# laser_driver_fet.net
KiCad netlist of a schematic drawn in EAGLE
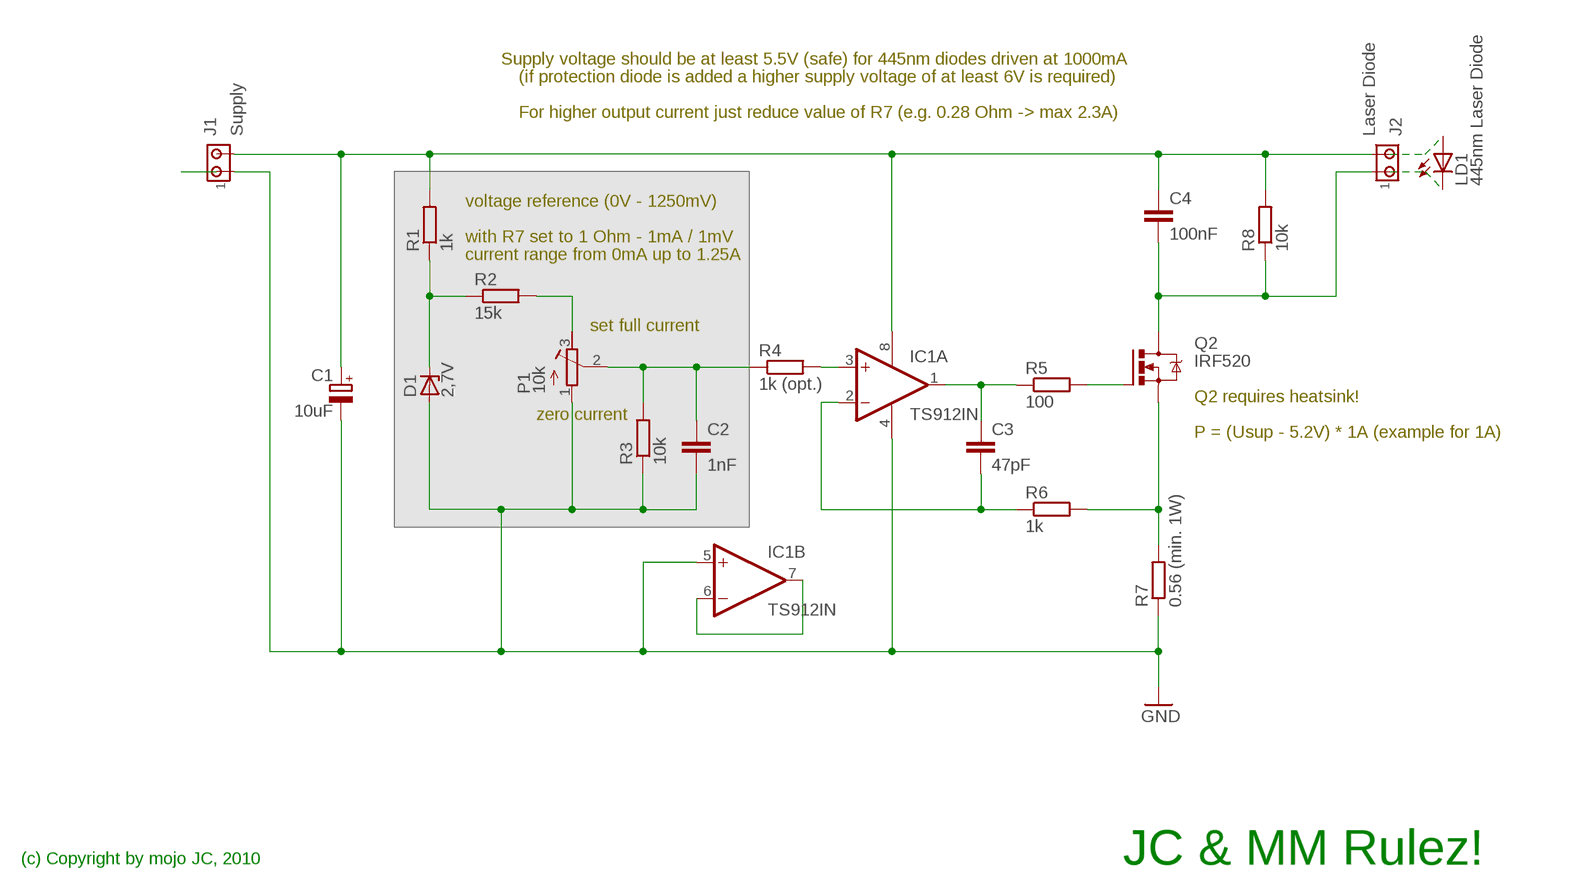
[diagram p0: schematic, sheet 1]

(export (version "E")
  (design (tool "Eeschema 10.0.6"))
  (components
    (comp (ref "C1")
      (value "10uF")
      (footprint "eagle-import:E5-13")
      (libsource (lib "eagle-import") (part "CPOL-EUE5-13"))
    )
    (comp (ref "C2")
      (value "1nF")
      (footprint "eagle-import:C2.5-3")
      (libsource (lib "eagle-import") (part "C2,5-3"))
    )
    (comp (ref "C3")
      (value "47pF")
      (footprint "eagle-import:C2.5-3")
      (libsource (lib "eagle-import") (part "C2,5-3"))
    )
    (comp (ref "C4")
      (value "100nF")
      (footprint "eagle-import:C2.5-3")
      (libsource (lib "eagle-import") (part "C2,5-3"))
    )
    (comp (ref "D1")
      (value "2,7V")
      (footprint "eagle-import:DO41Z10")
      (libsource (lib "eagle-import") (part "1N4728"))
    )
    (comp (ref "IC1")
      (value "TS912IN")
      (footprint "eagle-import:DIL08")
      (libsource (lib "eagle-import") (part "LM358N"))
    )
    (comp (ref "J1")
      (value "Supply")
      (footprint "eagle-import:1X2MTA")
      (libsource (lib "eagle-import") (part "MTA02-156"))
    )
    (comp (ref "J2")
      (value "Laser Diode")
      (footprint "eagle-import:1X2MTA")
      (libsource (lib "eagle-import") (part "MTA02-156"))
    )
    (comp (ref "LD1")
      (value "445nm Laser Diode")
      (footprint "eagle-import:LED5MM")
      (libsource (lib "eagle-import") (part "LED5MM"))
    )
    (comp (ref "P1")
      (value "10k")
      (footprint "eagle-import:RTRIM3296W")
      (libsource (lib "eagle-import") (part "R-TRIMM3296W"))
    )
    (comp (ref "Q2")
      (value "IRF520")
      (footprint "eagle-import:TO220BV")
      (libsource (lib "eagle-import") (part "IRF520"))
    )
    (comp (ref "R1")
      (value "1k")
      (footprint "eagle-import:0309_10")
      (libsource (lib "eagle-import") (part "R-EU_0309/10"))
    )
    (comp (ref "R2")
      (value "15k")
      (footprint "eagle-import:0309_10")
      (libsource (lib "eagle-import") (part "R-EU_0309/10"))
    )
    (comp (ref "R3")
      (value "10k")
      (footprint "eagle-import:0309_10")
      (libsource (lib "eagle-import") (part "R-EU_0309/10"))
    )
    (comp (ref "R4")
      (value "1k (opt.)")
      (footprint "eagle-import:0309_10")
      (libsource (lib "eagle-import") (part "R-EU_0309/10"))
    )
    (comp (ref "R5")
      (value "100")
      (footprint "eagle-import:0309_10")
      (libsource (lib "eagle-import") (part "R-EU_0309/10"))
    )
    (comp (ref "R6")
      (value "1k")
      (footprint "eagle-import:0309_10")
      (libsource (lib "eagle-import") (part "R-EU_0309/10"))
    )
    (comp (ref "R7")
      (value "0.56 (min. 1W)")
      (footprint "eagle-import:0411V")
      (libsource (lib "eagle-import") (part "R-EU_0411/3V"))
    )
    (comp (ref "R8")
      (value "10k")
      (footprint "eagle-import:0309_10")
      (libsource (lib "eagle-import") (part "R-EU_0309/10"))
    )
  )
  (nets
    (net (code "1") (name "GND") (class "Default")
      (node (ref "C1") (pin "-") (pinfunction "-_-") (pintype "passive"))
      (node (ref "C2") (pin "2") (pinfunction "2_2") (pintype "passive"))
      (node (ref "D1") (pin "A") (pinfunction "A_A") (pintype "passive"))
      (node (ref "IC1") (pin "4") (pinfunction "V-_4") (pintype "power_in"))
      (node (ref "IC1") (pin "5") (pinfunction "+IN_5") (pintype "input"))
      (node (ref "J1") (pin "1") (pinfunction "1_1") (pintype "passive"))
      (node (ref "P1") (pin "1") (pinfunction "E_1") (pintype "passive"))
      (node (ref "R3") (pin "1") (pinfunction "1_1") (pintype "passive"))
      (node (ref "R7") (pin "1") (pinfunction "1_1") (pintype "passive"))
    )
    (net (code "2") (name "Net-(C4-Pad2)") (class "Default")
      (node (ref "C4") (pin "2") (pinfunction "2_2") (pintype "passive"))
      (node (ref "J2") (pin "1") (pinfunction "1_1") (pintype "passive"))
      (node (ref "Q2") (pin "D") (pinfunction "D_D") (pintype "passive"))
      (node (ref "R8") (pin "1") (pinfunction "1_1") (pintype "passive"))
    )
    (net (code "3") (name "Net-(D1-PadC)") (class "Default")
      (node (ref "D1") (pin "C") (pinfunction "C_C") (pintype "passive"))
      (node (ref "R1") (pin "1") (pinfunction "1_1") (pintype "passive"))
      (node (ref "R2") (pin "1") (pinfunction "1_1") (pintype "passive"))
    )
    (net (code "4") (name "Net-(IC1A-+IN)") (class "Default")
      (node (ref "IC1") (pin "3") (pinfunction "+IN_3") (pintype "input"))
      (node (ref "R4") (pin "2") (pinfunction "2_2") (pintype "passive"))
    )
    (net (code "5") (name "Net-(IC1A--IN)") (class "Default")
      (node (ref "C3") (pin "2") (pinfunction "2_2") (pintype "passive"))
      (node (ref "IC1") (pin "2") (pinfunction "-IN_2") (pintype "input"))
      (node (ref "R6") (pin "1") (pinfunction "1_1") (pintype "passive"))
    )
    (net (code "6") (name "Net-(IC1A-OUT)") (class "Default")
      (node (ref "C3") (pin "1") (pinfunction "1_1") (pintype "passive"))
      (node (ref "IC1") (pin "1") (pinfunction "OUT_1") (pintype "output"))
      (node (ref "R5") (pin "1") (pinfunction "1_1") (pintype "passive"))
    )
    (net (code "7") (name "Net-(IC1B--IN)") (class "Default")
      (node (ref "IC1") (pin "6") (pinfunction "-IN_6") (pintype "input"))
      (node (ref "IC1") (pin "7") (pinfunction "OUT_7") (pintype "output"))
    )
    (net (code "8") (name "Net-(IC1C-V+)") (class "Default")
      (node (ref "C1") (pin "+") (pinfunction "+_+") (pintype "passive"))
      (node (ref "C4") (pin "1") (pinfunction "1_1") (pintype "passive"))
      (node (ref "IC1") (pin "8") (pinfunction "V+_8") (pintype "power_in"))
      (node (ref "J1") (pin "2") (pinfunction "2_2") (pintype "passive"))
      (node (ref "J2") (pin "2") (pinfunction "2_2") (pintype "passive"))
      (node (ref "R1") (pin "2") (pinfunction "2_2") (pintype "passive"))
      (node (ref "R8") (pin "2") (pinfunction "2_2") (pintype "passive"))
    )
    (net (code "9") (name "Net-(P1-A)") (class "Default")
      (node (ref "P1") (pin "3") (pinfunction "A_3") (pintype "passive"))
      (node (ref "R2") (pin "2") (pinfunction "2_2") (pintype "passive"))
    )
    (net (code "10") (name "Net-(P1-S)") (class "Default")
      (node (ref "C2") (pin "1") (pinfunction "1_1") (pintype "passive"))
      (node (ref "P1") (pin "2") (pinfunction "S_2") (pintype "passive"))
      (node (ref "R3") (pin "2") (pinfunction "2_2") (pintype "passive"))
      (node (ref "R4") (pin "1") (pinfunction "1_1") (pintype "passive"))
    )
    (net (code "11") (name "Net-(Q2-PadG)") (class "Default")
      (node (ref "Q2") (pin "G") (pinfunction "G_G") (pintype "passive"))
      (node (ref "R5") (pin "2") (pinfunction "2_2") (pintype "passive"))
    )
    (net (code "12") (name "Net-(Q2-PadS)") (class "Default")
      (node (ref "Q2") (pin "S") (pinfunction "S_S") (pintype "passive"))
      (node (ref "R6") (pin "2") (pinfunction "2_2") (pintype "passive"))
      (node (ref "R7") (pin "2") (pinfunction "2_2") (pintype "passive"))
    )
    (net (code "13") (name "unconnected-(LD1-C-PadK)") (class "Default")
      (node (ref "LD1") (pin "K") (pinfunction "C_K") (pintype "passive"))
    )
    (net (code "14") (name "unconnected-(LD1-PadA)") (class "Default")
      (node (ref "LD1") (pin "A") (pinfunction "A_A") (pintype "passive"))
    )
  )
)
